# 03_MCU.net
KiCad netlist of a schematic drawn in Altium Designer
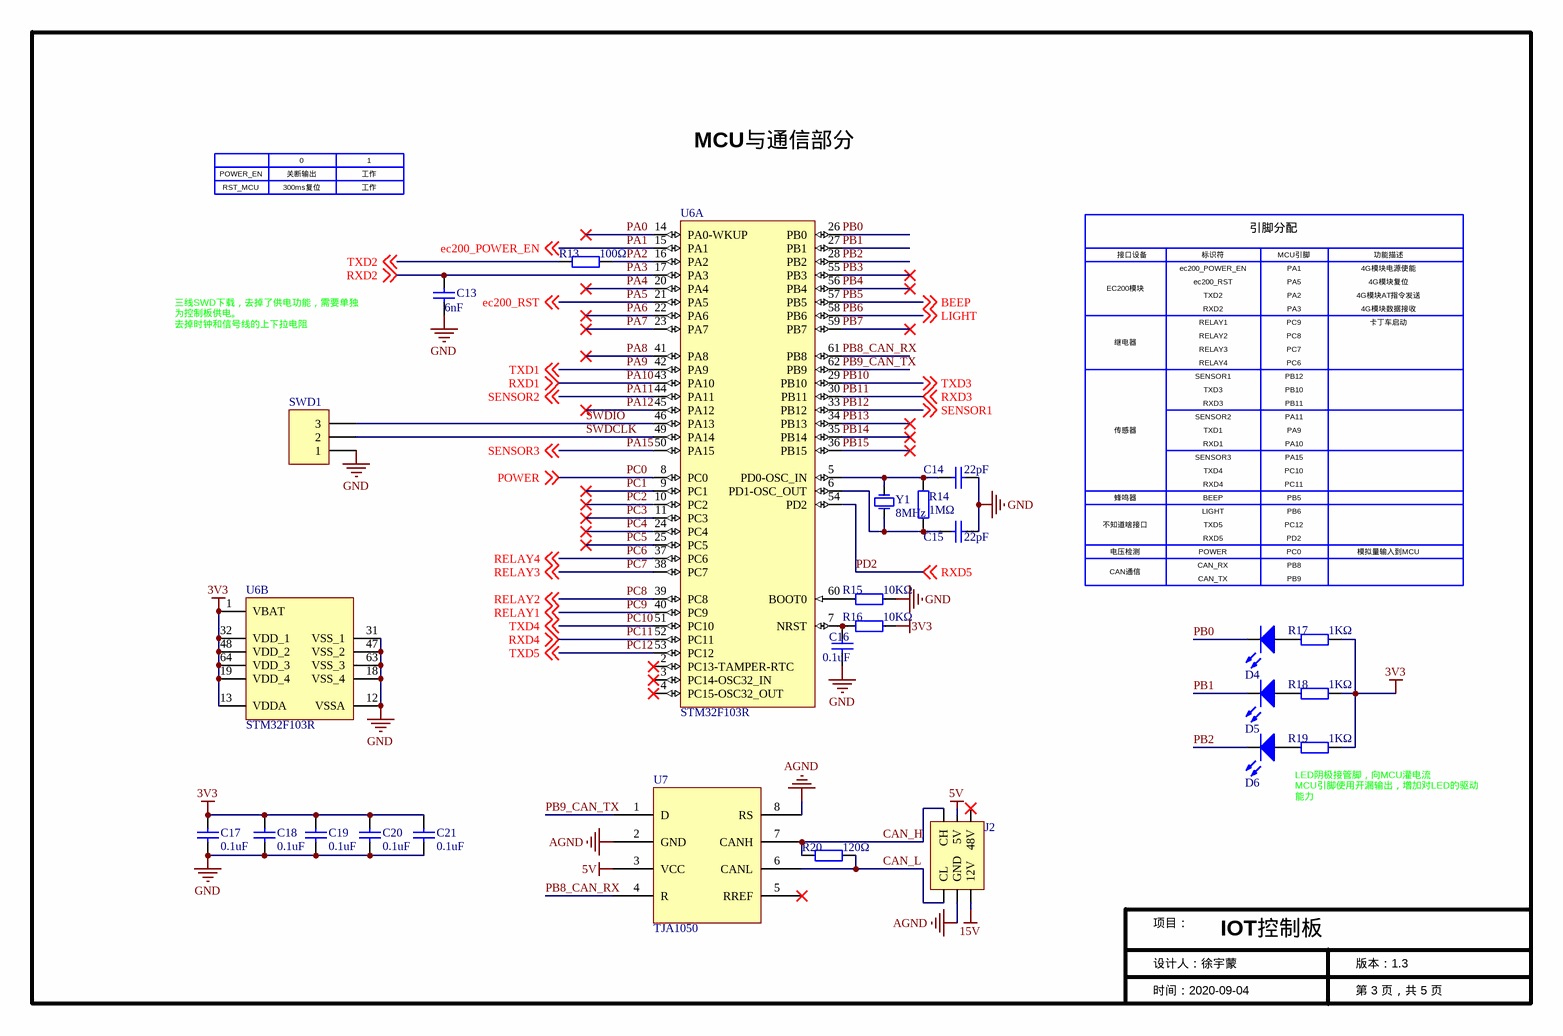
[diagram p0: 03_MCU部分.SchDoc]

(export (version "E")
  (design (tool "Eeschema 10.0.6"))
  (components
    (comp (ref "C13")
      (value "6nF")
      (footprint "CAP-0603")
      (description "无极性电容")
      (fields (field (name "Comment") "Cap") (field (name "PUBLISHER") "Altium Limited"))
      (libsource (lib "Arrowy_Racing") (part "Cap"))
    )
    (comp (ref "C14")
      (value "22pF")
      (footprint "CAP-0603")
      (description "无极性电容")
      (fields (field (name "Comment") "Cap") (field (name "PUBLISHER") "Altium Limited"))
      (libsource (lib "Arrowy_Racing") (part "Cap"))
    )
    (comp (ref "C15")
      (value "22pF")
      (footprint "CAP-0603")
      (description "无极性电容")
      (fields (field (name "Comment") "Cap") (field (name "PUBLISHER") "Altium Limited"))
      (libsource (lib "Arrowy_Racing") (part "Cap"))
    )
    (comp (ref "C16")
      (value "0.1uF")
      (footprint "CAP-0603")
      (description "无极性电容")
      (fields (field (name "Comment") "Cap") (field (name "PUBLISHER") "Altium Limited"))
      (libsource (lib "Arrowy_Racing") (part "Cap"))
    )
    (comp (ref "C17")
      (value "0.1uF")
      (footprint "CAP-0603")
      (description "无极性电容")
      (fields (field (name "Comment") "Cap") (field (name "PUBLISHER") "Altium Limited"))
      (libsource (lib "Arrowy_Racing") (part "Cap"))
    )
    (comp (ref "C18")
      (value "0.1uF")
      (footprint "CAP-0603")
      (description "无极性电容")
      (fields (field (name "Comment") "Cap") (field (name "PUBLISHER") "Altium Limited"))
      (libsource (lib "Arrowy_Racing") (part "Cap"))
    )
    (comp (ref "C19")
      (value "0.1uF")
      (footprint "CAP-0603")
      (description "无极性电容")
      (fields (field (name "Comment") "Cap") (field (name "PUBLISHER") "Altium Limited"))
      (libsource (lib "Arrowy_Racing") (part "Cap"))
    )
    (comp (ref "C20")
      (value "0.1uF")
      (footprint "CAP-0603")
      (description "无极性电容")
      (fields (field (name "Comment") "Cap") (field (name "PUBLISHER") "Altium Limited"))
      (libsource (lib "Arrowy_Racing") (part "Cap"))
    )
    (comp (ref "C21")
      (value "0.1uF")
      (footprint "CAP-0603")
      (description "无极性电容")
      (fields (field (name "Comment") "Cap") (field (name "PUBLISHER") "Altium Limited"))
      (libsource (lib "Arrowy_Racing") (part "Cap"))
    )
    (comp (ref "D4")
      (value "LED")
      (footprint "LED_0805")
      (description "发光二极管")
      (fields (field (name "PUBLISHER") "Altium Limited"))
      (libsource (lib "Arrowy_Racing") (part "LED"))
    )
    (comp (ref "D5")
      (value "LED")
      (footprint "LED_0805")
      (description "发光二极管")
      (fields (field (name "PUBLISHER") "Altium Limited"))
      (libsource (lib "Arrowy_Racing") (part "LED"))
    )
    (comp (ref "D6")
      (value "LED")
      (footprint "LED_0805")
      (description "发光二极管")
      (fields (field (name "PUBLISHER") "Altium Limited"))
      (libsource (lib "Arrowy_Racing") (part "LED"))
    )
    (comp (ref "J2") (value "标准接口") (footprint "标准接口-直插-灰色") (libsource (lib "Arrowy_Racing") (part "标准接口")))
    (comp (ref "R13")
      (value "100Ω")
      (footprint "0603")
      (description "贴片电阻")
      (fields (field (name "Comment") "Res") (field (name "PUBLISHER") "Altium Limited"))
      (libsource (lib "Arrowy_Racing") (part "Res"))
    )
    (comp (ref "R14")
      (value "1MΩ")
      (footprint "0603")
      (description "贴片电阻")
      (fields (field (name "Comment") "Res") (field (name "PUBLISHER") "Altium Limited"))
      (libsource (lib "") (part "Res_1"))
    )
    (comp (ref "R15")
      (value "10KΩ")
      (footprint "0603")
      (description "贴片电阻")
      (fields (field (name "Comment") "Res") (field (name "PUBLISHER") "Altium Limited"))
      (libsource (lib "Arrowy_Racing") (part "Res"))
    )
    (comp (ref "R16")
      (value "10KΩ")
      (footprint "0603")
      (description "贴片电阻")
      (fields (field (name "Comment") "Res") (field (name "PUBLISHER") "Altium Limited"))
      (libsource (lib "Arrowy_Racing") (part "Res"))
    )
    (comp (ref "R17")
      (value "1KΩ")
      (footprint "0603")
      (description "贴片电阻")
      (fields (field (name "Comment") "Res") (field (name "PUBLISHER") "Altium Limited"))
      (libsource (lib "Arrowy_Racing") (part "Res"))
    )
    (comp (ref "R18")
      (value "1KΩ")
      (footprint "0603")
      (description "贴片电阻")
      (fields (field (name "Comment") "Res") (field (name "PUBLISHER") "Altium Limited"))
      (libsource (lib "Arrowy_Racing") (part "Res"))
    )
    (comp (ref "R19")
      (value "1KΩ")
      (footprint "0603")
      (description "贴片电阻")
      (fields (field (name "Comment") "Res") (field (name "PUBLISHER") "Altium Limited"))
      (libsource (lib "Arrowy_Racing") (part "Res"))
    )
    (comp (ref "R20")
      (value "120Ω")
      (footprint "0603")
      (description "贴片电阻")
      (fields (field (name "Comment") "Res") (field (name "PUBLISHER") "Altium Limited"))
      (libsource (lib "Arrowy_Racing") (part "Res"))
    )
    (comp (ref "SWD1")
      (value "Header3")
      (footprint "Header_3X1_2.54_排针")
      (description "接插件")
      (libsource (lib "Arrowy_Racing") (part "Header3"))
    )
    (comp (ref "U6")
      (value "STM32F103R")
      (footprint "LQFP64")
      (description "STM32单片机64引脚")
      (fields (field (name "PARTNUMBER") "STM32F103RGT6"))
      (libsource (lib "Arrowy_Racing") (part "STM32F103R"))
    )
    (comp (ref "U7")
      (value "TJA1050")
      (footprint "TJA1050")
      (description "CAN收发器芯片")
      (libsource (lib "PCBSchlib_SEU_RobotLab") (part "TJA1050"))
    )
    (comp (ref "Y1")
      (value "8MHz")
      (footprint "X-SM49")
      (description "晶振")
      (fields (field (name "Comment") "XTAL") (field (name "PUBLISHER") "Altium Limited"))
      (libsource (lib "Arrowy_Racing") (part "XTAL"))
    )
  )
  (nets
    (net (code "1") (name "/CAN_H") (class "Default")
      (node (ref "J2") (pin "5") (pinfunction "CH_5") (pintype "passive"))
      (node (ref "R20") (pin "2") (pinfunction "2_2") (pintype "passive"))
      (node (ref "U7") (pin "7") (pinfunction "CANH_7") (pintype "passive"))
    )
    (net (code "2") (name "/CAN_L") (class "Default")
      (node (ref "J2") (pin "6") (pinfunction "CL_6") (pintype "passive"))
      (node (ref "R20") (pin "1") (pinfunction "1_1") (pintype "passive"))
      (node (ref "U7") (pin "6") (pinfunction "CANL_6") (pintype "passive"))
    )
    (net (code "3") (name "/PA0") (class "Default")
      (node (ref "U6") (pin "14") (pinfunction "PA0-WKUP_14") (pintype "bidirectional+no_connect"))
    )
    (net (code "4") (name "/PA2") (class "Default")
      (node (ref "R13") (pin "1") (pinfunction "1_1") (pintype "passive"))
      (node (ref "U6") (pin "16") (pinfunction "PA2_16") (pintype "bidirectional"))
    )
    (net (code "5") (name "/PA4") (class "Default")
      (node (ref "U6") (pin "20") (pinfunction "PA4_20") (pintype "bidirectional+no_connect"))
    )
    (net (code "6") (name "/PA6") (class "Default")
      (node (ref "U6") (pin "22") (pinfunction "PA6_22") (pintype "bidirectional+no_connect"))
    )
    (net (code "7") (name "/PA7") (class "Default")
      (node (ref "U6") (pin "23") (pinfunction "PA7_23") (pintype "bidirectional+no_connect"))
    )
    (net (code "8") (name "/PA8") (class "Default")
      (node (ref "U6") (pin "41") (pinfunction "PA8_41") (pintype "bidirectional+no_connect"))
    )
    (net (code "9") (name "/PA12") (class "Default")
      (node (ref "U6") (pin "45") (pinfunction "PA12_45") (pintype "bidirectional+no_connect"))
    )
    (net (code "10") (name "/PB0") (class "Default")
      (node (ref "D4") (pin "2") (pinfunction "K_2") (pintype "passive"))
      (node (ref "U6") (pin "26") (pinfunction "PB0_26") (pintype "bidirectional"))
    )
    (net (code "11") (name "/PB1") (class "Default")
      (node (ref "D5") (pin "2") (pinfunction "K_2") (pintype "passive"))
      (node (ref "U6") (pin "27") (pinfunction "PB1_27") (pintype "bidirectional"))
    )
    (net (code "12") (name "/PB2") (class "Default")
      (node (ref "D6") (pin "2") (pinfunction "K_2") (pintype "passive"))
      (node (ref "U6") (pin "28") (pinfunction "PB2_28") (pintype "bidirectional"))
    )
    (net (code "13") (name "/PB3") (class "Default")
      (node (ref "U6") (pin "55") (pinfunction "PB3_55") (pintype "bidirectional+no_connect"))
    )
    (net (code "14") (name "/PB4") (class "Default")
      (node (ref "U6") (pin "56") (pinfunction "PB4_56") (pintype "bidirectional+no_connect"))
    )
    (net (code "15") (name "/PB7") (class "Default")
      (node (ref "U6") (pin "59") (pinfunction "PB7_59") (pintype "bidirectional+no_connect"))
    )
    (net (code "16") (name "/PB8_CAN_RX") (class "Default")
      (node (ref "U6") (pin "61") (pinfunction "PB8_61") (pintype "bidirectional"))
      (node (ref "U7") (pin "4") (pinfunction "R_4") (pintype "passive"))
    )
    (net (code "17") (name "/PB9_CAN_TX") (class "Default")
      (node (ref "U6") (pin "62") (pinfunction "PB9_62") (pintype "bidirectional"))
      (node (ref "U7") (pin "1") (pinfunction "D_1") (pintype "passive"))
    )
    (net (code "18") (name "/PB13") (class "Default")
      (node (ref "U6") (pin "34") (pinfunction "PB13_34") (pintype "bidirectional+no_connect"))
    )
    (net (code "19") (name "/PB14") (class "Default")
      (node (ref "U6") (pin "35") (pinfunction "PB14_35") (pintype "bidirectional+no_connect"))
    )
    (net (code "20") (name "/PB15") (class "Default")
      (node (ref "U6") (pin "36") (pinfunction "PB15_36") (pintype "bidirectional+no_connect"))
    )
    (net (code "21") (name "/PC1") (class "Default")
      (node (ref "U6") (pin "9") (pinfunction "PC1_9") (pintype "bidirectional+no_connect"))
    )
    (net (code "22") (name "/PC2") (class "Default")
      (node (ref "U6") (pin "10") (pinfunction "PC2_10") (pintype "bidirectional+no_connect"))
    )
    (net (code "23") (name "/PC3") (class "Default")
      (node (ref "U6") (pin "11") (pinfunction "PC3_11") (pintype "bidirectional+no_connect"))
    )
    (net (code "24") (name "/PC4") (class "Default")
      (node (ref "U6") (pin "24") (pinfunction "PC4_24") (pintype "bidirectional+no_connect"))
    )
    (net (code "25") (name "/PC5") (class "Default")
      (node (ref "U6") (pin "25") (pinfunction "PC5_25") (pintype "bidirectional+no_connect"))
    )
    (net (code "26") (name "/SWDCLK") (class "Default")
      (node (ref "SWD1") (pin "2") (pinfunction "2_2") (pintype "passive"))
      (node (ref "U6") (pin "49") (pinfunction "PA14_49") (pintype "bidirectional"))
    )
    (net (code "27") (name "/SWDIO") (class "Default")
      (node (ref "SWD1") (pin "3") (pinfunction "3_3") (pintype "passive"))
      (node (ref "U6") (pin "46") (pinfunction "PA13_46") (pintype "bidirectional"))
    )
    (net (code "28") (name "3V3") (class "Default")
      (node (ref "C17") (pin "2") (pinfunction "2_2") (pintype "passive"))
      (node (ref "C18") (pin "2") (pinfunction "2_2") (pintype "passive"))
      (node (ref "C19") (pin "2") (pinfunction "2_2") (pintype "passive"))
      (node (ref "C20") (pin "2") (pinfunction "2_2") (pintype "passive"))
      (node (ref "C21") (pin "2") (pinfunction "2_2") (pintype "passive"))
      (node (ref "R16") (pin "1") (pinfunction "1_1") (pintype "passive"))
      (node (ref "R17") (pin "1") (pinfunction "1_1") (pintype "passive"))
      (node (ref "R18") (pin "1") (pinfunction "1_1") (pintype "passive"))
      (node (ref "R19") (pin "1") (pinfunction "1_1") (pintype "passive"))
      (node (ref "U6") (pin "1") (pinfunction "VBAT_1") (pintype "power_in"))
      (node (ref "U6") (pin "13") (pinfunction "VDDA_13") (pintype "power_in"))
      (node (ref "U6") (pin "19") (pinfunction "VDD_4_19") (pintype "power_in"))
      (node (ref "U6") (pin "32") (pinfunction "VDD_1_32") (pintype "power_in"))
      (node (ref "U6") (pin "48") (pinfunction "VDD_2_48") (pintype "power_in"))
      (node (ref "U6") (pin "64") (pinfunction "VDD_3_64") (pintype "power_in"))
    )
    (net (code "29") (name "5V") (class "Default")
      (node (ref "J2") (pin "3") (pinfunction "5V_3") (pintype "passive"))
      (node (ref "U7") (pin "3") (pinfunction "VCC_3") (pintype "passive"))
    )
    (net (code "30") (name "15V") (class "Default")
      (node (ref "J2") (pin "2") (pinfunction "12V_2") (pintype "passive"))
    )
    (net (code "31") (name "AGND") (class "Default")
      (node (ref "J2") (pin "4") (pinfunction "GND_4") (pintype "passive"))
      (node (ref "U7") (pin "2") (pinfunction "GND_2") (pintype "passive"))
      (node (ref "U7") (pin "8") (pinfunction "RS_8") (pintype "passive"))
    )
    (net (code "32") (name "BEEP") (class "Default")
      (node (ref "U6") (pin "57") (pinfunction "PB5_57") (pintype "bidirectional"))
    )
    (net (code "33") (name "GND") (class "Default")
      (node (ref "C13") (pin "2") (pinfunction "2_2") (pintype "passive"))
      (node (ref "C14") (pin "1") (pinfunction "1_1") (pintype "passive"))
      (node (ref "C15") (pin "1") (pinfunction "1_1") (pintype "passive"))
      (node (ref "C16") (pin "1") (pinfunction "1_1") (pintype "passive"))
      (node (ref "C17") (pin "1") (pinfunction "1_1") (pintype "passive"))
      (node (ref "C18") (pin "1") (pinfunction "1_1") (pintype "passive"))
      (node (ref "C19") (pin "1") (pinfunction "1_1") (pintype "passive"))
      (node (ref "C20") (pin "1") (pinfunction "1_1") (pintype "passive"))
      (node (ref "C21") (pin "1") (pinfunction "1_1") (pintype "passive"))
      (node (ref "R15") (pin "1") (pinfunction "1_1") (pintype "passive"))
      (node (ref "SWD1") (pin "1") (pinfunction "1_1") (pintype "passive"))
      (node (ref "U6") (pin "12") (pinfunction "VSSA_12") (pintype "power_in"))
      (node (ref "U6") (pin "18") (pinfunction "VSS_4_18") (pintype "power_in"))
      (node (ref "U6") (pin "31") (pinfunction "VSS_1_31") (pintype "power_in"))
      (node (ref "U6") (pin "47") (pinfunction "VSS_2_47") (pintype "power_in"))
      (node (ref "U6") (pin "63") (pinfunction "VSS_3_63") (pintype "power_in"))
    )
    (net (code "34") (name "LIGHT") (class "Default")
      (node (ref "U6") (pin "58") (pinfunction "PB6_58") (pintype "bidirectional"))
    )
    (net (code "35") (name "Net-(D4-A)") (class "Default")
      (node (ref "D4") (pin "1") (pinfunction "A_1") (pintype "passive"))
      (node (ref "R17") (pin "2") (pinfunction "2_2") (pintype "passive"))
    )
    (net (code "36") (name "Net-(D5-A)") (class "Default")
      (node (ref "D5") (pin "1") (pinfunction "A_1") (pintype "passive"))
      (node (ref "R18") (pin "2") (pinfunction "2_2") (pintype "passive"))
    )
    (net (code "37") (name "Net-(D6-A)") (class "Default")
      (node (ref "D6") (pin "1") (pinfunction "A_1") (pintype "passive"))
      (node (ref "R19") (pin "2") (pinfunction "2_2") (pintype "passive"))
    )
    (net (code "38") (name "Net-(U6A-BOOT0)") (class "Default")
      (node (ref "R15") (pin "2") (pinfunction "2_2") (pintype "passive"))
      (node (ref "U6") (pin "60") (pinfunction "BOOT0_60") (pintype "input"))
    )
    (net (code "39") (name "Net-(U6A-NRST)") (class "Default")
      (node (ref "C16") (pin "2") (pinfunction "2_2") (pintype "passive"))
      (node (ref "R16") (pin "2") (pinfunction "2_2") (pintype "passive"))
      (node (ref "U6") (pin "7") (pinfunction "NRST_7") (pintype "bidirectional"))
    )
    (net (code "40") (name "Net-(U6A-PD0-OSC_IN)") (class "Default")
      (node (ref "C14") (pin "2") (pinfunction "2_2") (pintype "passive"))
      (node (ref "R14") (pin "2") (pinfunction "2_2") (pintype "passive"))
      (node (ref "U6") (pin "5") (pinfunction "PD0-OSC_IN_5") (pintype "bidirectional"))
      (node (ref "Y1") (pin "2") (pinfunction "2_2") (pintype "passive"))
    )
    (net (code "41") (name "Net-(U6A-PD1-OSC_OUT)") (class "Default")
      (node (ref "C15") (pin "2") (pinfunction "2_2") (pintype "passive"))
      (node (ref "R14") (pin "1") (pinfunction "1_1") (pintype "passive"))
      (node (ref "U6") (pin "6") (pinfunction "PD1-OSC_OUT_6") (pintype "bidirectional"))
      (node (ref "Y1") (pin "1") (pinfunction "1_1") (pintype "passive"))
    )
    (net (code "42") (name "POWER") (class "Default")
      (node (ref "U6") (pin "8") (pinfunction "PC0_8") (pintype "bidirectional"))
    )
    (net (code "43") (name "RELAY1") (class "Default")
      (node (ref "U6") (pin "40") (pinfunction "PC9_40") (pintype "bidirectional"))
    )
    (net (code "44") (name "RELAY2") (class "Default")
      (node (ref "U6") (pin "39") (pinfunction "PC8_39") (pintype "bidirectional"))
    )
    (net (code "45") (name "RELAY3") (class "Default")
      (node (ref "U6") (pin "38") (pinfunction "PC7_38") (pintype "bidirectional"))
    )
    (net (code "46") (name "RELAY4") (class "Default")
      (node (ref "U6") (pin "37") (pinfunction "PC6_37") (pintype "bidirectional"))
    )
    (net (code "47") (name "RXD1") (class "Default")
      (node (ref "U6") (pin "43") (pinfunction "PA10_43") (pintype "bidirectional"))
    )
    (net (code "48") (name "RXD2") (class "Default")
      (node (ref "C13") (pin "1") (pinfunction "1_1") (pintype "passive"))
      (node (ref "U6") (pin "17") (pinfunction "PA3_17") (pintype "bidirectional"))
    )
    (net (code "49") (name "RXD3") (class "Default")
      (node (ref "U6") (pin "30") (pinfunction "PB11_30") (pintype "bidirectional"))
    )
    (net (code "50") (name "RXD4") (class "Default")
      (node (ref "U6") (pin "52") (pinfunction "PC11_52") (pintype "bidirectional"))
    )
    (net (code "51") (name "RXD5") (class "Default")
      (node (ref "U6") (pin "54") (pinfunction "PD2_54") (pintype "bidirectional"))
    )
    (net (code "52") (name "SENSOR1") (class "Default")
      (node (ref "U6") (pin "33") (pinfunction "PB12_33") (pintype "bidirectional"))
    )
    (net (code "53") (name "SENSOR2") (class "Default")
      (node (ref "U6") (pin "44") (pinfunction "PA11_44") (pintype "bidirectional"))
    )
    (net (code "54") (name "SENSOR3") (class "Default")
      (node (ref "U6") (pin "50") (pinfunction "PA15_50") (pintype "bidirectional"))
    )
    (net (code "55") (name "TXD1") (class "Default")
      (node (ref "U6") (pin "42") (pinfunction "PA9_42") (pintype "bidirectional"))
    )
    (net (code "56") (name "TXD2") (class "Default")
      (node (ref "R13") (pin "2") (pinfunction "2_2") (pintype "passive"))
    )
    (net (code "57") (name "TXD3") (class "Default")
      (node (ref "U6") (pin "29") (pinfunction "PB10_29") (pintype "bidirectional"))
    )
    (net (code "58") (name "TXD4") (class "Default")
      (node (ref "U6") (pin "51") (pinfunction "PC10_51") (pintype "bidirectional"))
    )
    (net (code "59") (name "TXD5") (class "Default")
      (node (ref "U6") (pin "53") (pinfunction "PC12_53") (pintype "bidirectional"))
    )
    (net (code "60") (name "ec200_POWER_EN") (class "Default")
      (node (ref "U6") (pin "15") (pinfunction "PA1_15") (pintype "bidirectional"))
    )
    (net (code "61") (name "ec200_RST") (class "Default")
      (node (ref "U6") (pin "21") (pinfunction "PA5_21") (pintype "bidirectional"))
    )
    (net (code "62") (name "unconnected-(J2-48V-Pad1)") (class "Default")
      (node (ref "J2") (pin "1") (pinfunction "48V_1") (pintype "passive+no_connect"))
    )
    (net (code "63") (name "unconnected-(U6A-PC13-TAMPER-RTC-Pad2)") (class "Default")
      (node (ref "U6") (pin "2") (pinfunction "PC13-TAMPER-RTC_2") (pintype "bidirectional+no_connect"))
    )
    (net (code "64") (name "unconnected-(U6A-PC14-OSC32_IN-Pad3)") (class "Default")
      (node (ref "U6") (pin "3") (pinfunction "PC14-OSC32_IN_3") (pintype "bidirectional+no_connect"))
    )
    (net (code "65") (name "unconnected-(U6A-PC15-OSC32_OUT-Pad4)") (class "Default")
      (node (ref "U6") (pin "4") (pinfunction "PC15-OSC32_OUT_4") (pintype "bidirectional+no_connect"))
    )
    (net (code "66") (name "unconnected-(U7-RREF-Pad5)") (class "Default")
      (node (ref "U7") (pin "5") (pinfunction "RREF_5") (pintype "passive+no_connect"))
    )
  )
)
